# CanBus-UP-Schalter-Teil1.net
KiCad netlist of a schematic drawn in EAGLE
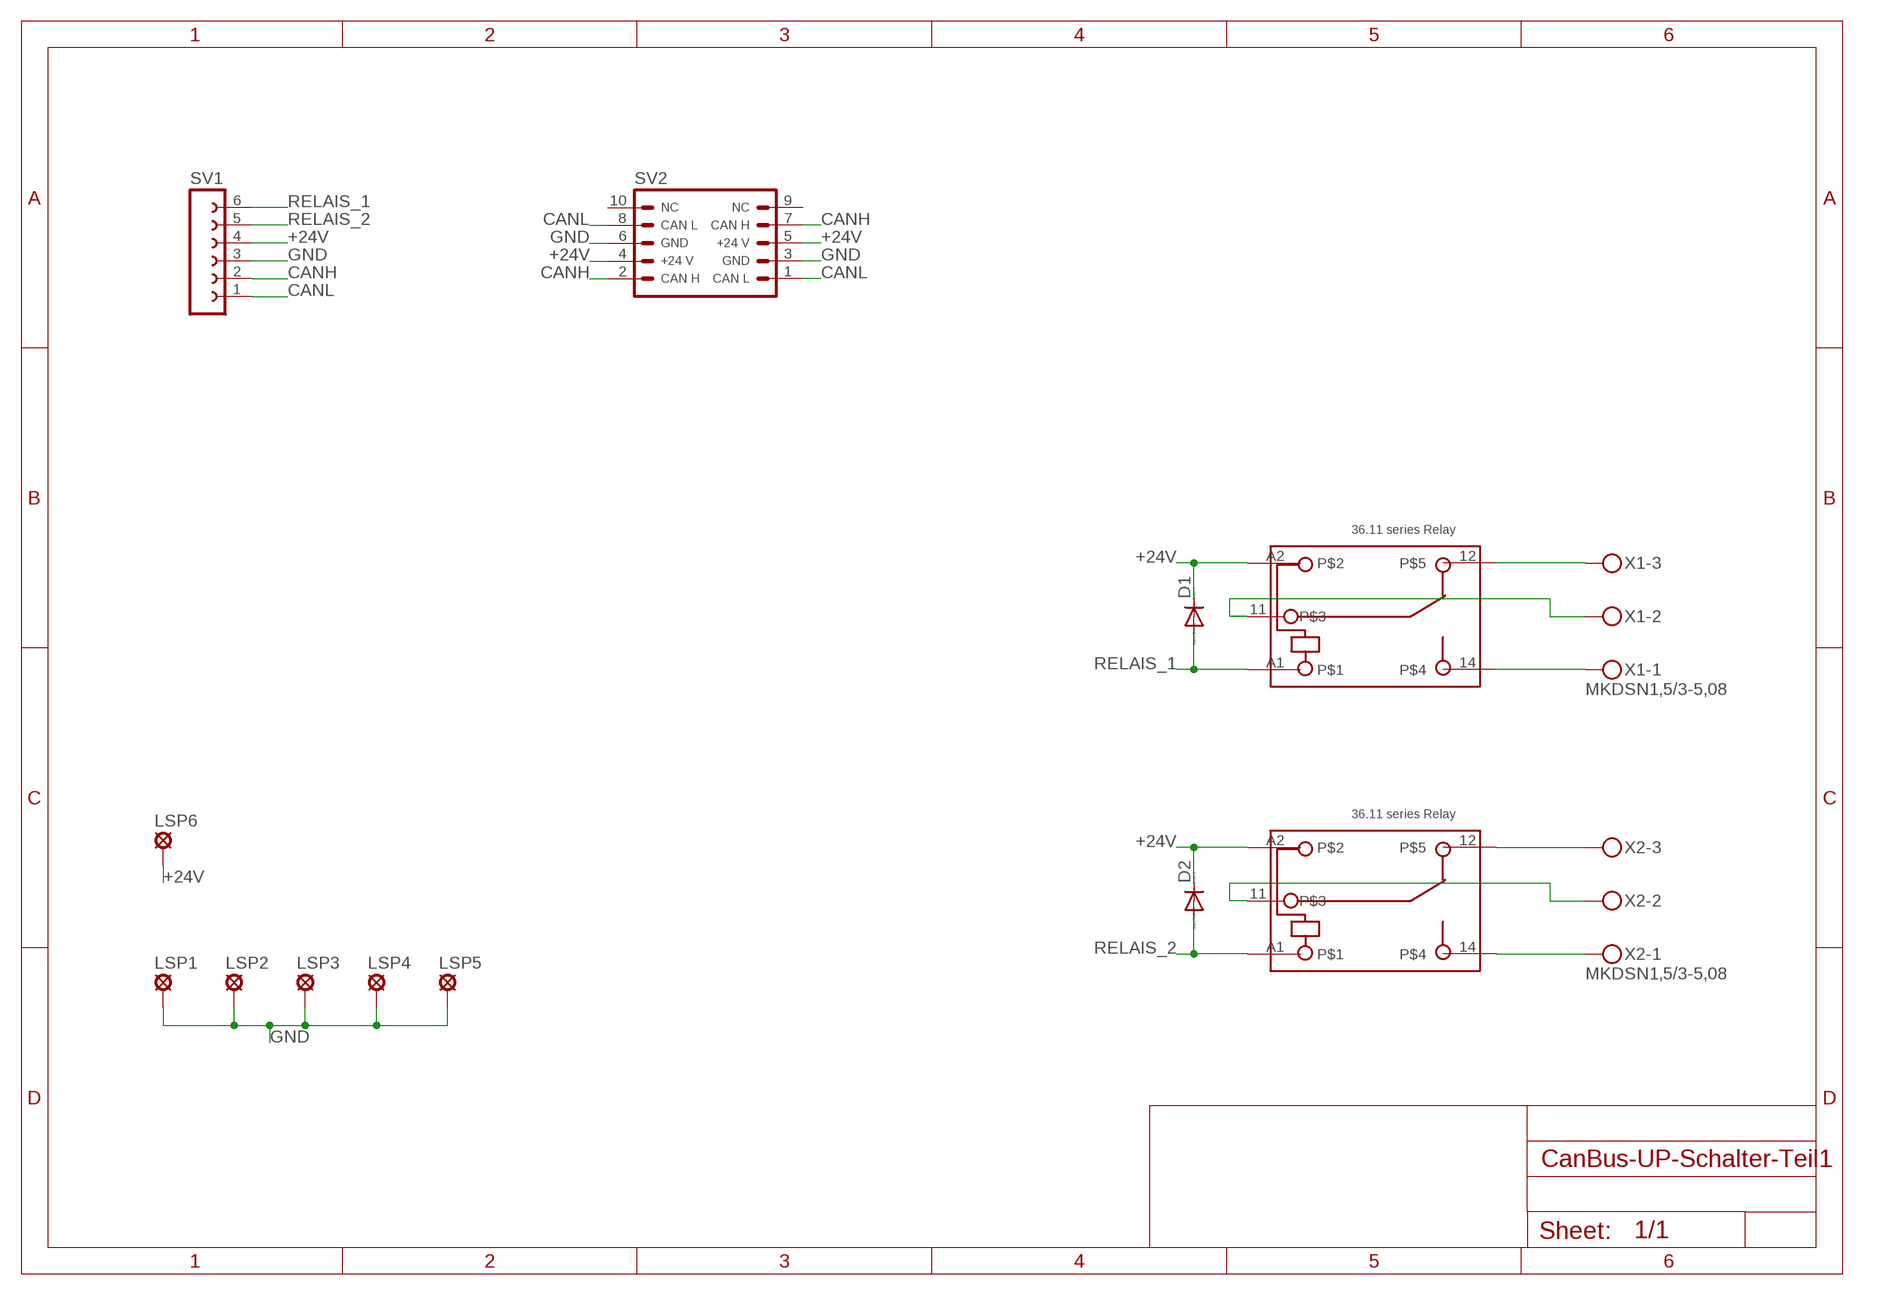
[diagram p0: schematic, sheet 1]

(export (version "E")
  (design (tool "Eeschema 10.0.6"))
  (components
    (comp (ref "D1")
      (value "DIODE-SOD323-R")
      (footprint "eagle-import:SOD323-R")
      (libsource (lib "eagle-import") (part "DIODE-SOD323-R"))
    )
    (comp (ref "D2")
      (value "DIODE-SOD323-R")
      (footprint "eagle-import:SOD323-R")
      (libsource (lib "eagle-import") (part "DIODE-SOD323-R"))
    )
    (comp (ref "K1")
      (value "36.11")
      (footprint "eagle-import:36.11")
      (libsource (lib "eagle-import") (part "36.11"))
    )
    (comp (ref "K2")
      (value "36.11")
      (footprint "eagle-import:36.11")
      (libsource (lib "eagle-import") (part "36.11"))
    )
    (comp (ref "LSP1")
      (value "LSP13")
      (footprint "eagle-import:LSP13")
      (libsource (lib "eagle-import") (part "LSP13"))
    )
    (comp (ref "LSP2")
      (value "LSP13")
      (footprint "eagle-import:LSP13")
      (libsource (lib "eagle-import") (part "LSP13"))
    )
    (comp (ref "LSP3")
      (value "LSP13")
      (footprint "eagle-import:LSP13")
      (libsource (lib "eagle-import") (part "LSP13"))
    )
    (comp (ref "LSP4")
      (value "LSP13")
      (footprint "eagle-import:LSP13")
      (libsource (lib "eagle-import") (part "LSP13"))
    )
    (comp (ref "LSP5")
      (value "LSP13")
      (footprint "eagle-import:LSP13")
      (libsource (lib "eagle-import") (part "LSP13"))
    )
    (comp (ref "LSP6")
      (value "LSP13")
      (footprint "eagle-import:LSP13")
      (libsource (lib "eagle-import") (part "LSP13"))
    )
    (comp (ref "SV1")
      (value "FE06-1")
      (footprint "eagle-import:FE06")
      (libsource (lib "eagle-import") (part "FE06-1"))
    )
    (comp (ref "SV2")
      (value "ML10L")
      (footprint "eagle-import:ML10L")
      (libsource (lib "eagle-import") (part "ML10L"))
    )
    (comp (ref "X1")
      (value "MKDSN1,5/3-5,08")
      (footprint "eagle-import:MKDSN1,5_3-5,08")
      (libsource (lib "eagle-import") (part "MKDSN1,5/3-5,08"))
    )
    (comp (ref "X2")
      (value "MKDSN1,5/3-5,08")
      (footprint "eagle-import:MKDSN1,5_3-5,08")
      (libsource (lib "eagle-import") (part "MKDSN1,5/3-5,08"))
    )
  )
  (nets
    (net (code "1") (name "/+24V") (class "Default")
      (node (ref "D1") (pin "C") (pinfunction "C_C") (pintype "passive"))
      (node (ref "D2") (pin "C") (pinfunction "C_C") (pintype "passive"))
      (node (ref "K1") (pin "A2") (pinfunction "P$2_A2") (pintype "passive"))
      (node (ref "K2") (pin "A2") (pinfunction "P$2_A2") (pintype "passive"))
      (node (ref "LSP6") (pin "MP") (pinfunction "MP_MP") (pintype "passive"))
      (node (ref "SV1") (pin "4") (pinfunction "4_4") (pintype "passive"))
      (node (ref "SV2") (pin "4") (pinfunction "4_4") (pintype "passive"))
      (node (ref "SV2") (pin "5") (pinfunction "5_5") (pintype "passive"))
    )
    (net (code "2") (name "/CANH") (class "Default")
      (node (ref "SV1") (pin "2") (pinfunction "2_2") (pintype "passive"))
      (node (ref "SV2") (pin "2") (pinfunction "2_2") (pintype "passive"))
      (node (ref "SV2") (pin "7") (pinfunction "7_7") (pintype "passive"))
    )
    (net (code "3") (name "/CANL") (class "Default")
      (node (ref "SV1") (pin "1") (pinfunction "1_1") (pintype "passive"))
      (node (ref "SV2") (pin "1") (pinfunction "1_1") (pintype "passive"))
      (node (ref "SV2") (pin "8") (pinfunction "8_8") (pintype "passive"))
    )
    (net (code "4") (name "/GND") (class "Default")
      (node (ref "LSP1") (pin "MP") (pinfunction "MP_MP") (pintype "passive"))
      (node (ref "LSP2") (pin "MP") (pinfunction "MP_MP") (pintype "passive"))
      (node (ref "LSP3") (pin "MP") (pinfunction "MP_MP") (pintype "passive"))
      (node (ref "LSP4") (pin "MP") (pinfunction "MP_MP") (pintype "passive"))
      (node (ref "LSP5") (pin "MP") (pinfunction "MP_MP") (pintype "passive"))
      (node (ref "SV1") (pin "3") (pinfunction "3_3") (pintype "passive"))
      (node (ref "SV2") (pin "3") (pinfunction "3_3") (pintype "passive"))
      (node (ref "SV2") (pin "6") (pinfunction "6_6") (pintype "passive"))
    )
    (net (code "5") (name "/RELAIS_1") (class "Default")
      (node (ref "D1") (pin "A") (pinfunction "A_A") (pintype "passive"))
      (node (ref "K1") (pin "A1") (pinfunction "P$1_A1") (pintype "passive"))
      (node (ref "SV1") (pin "6") (pinfunction "6_6") (pintype "passive"))
    )
    (net (code "6") (name "/RELAIS_2") (class "Default")
      (node (ref "D2") (pin "A") (pinfunction "A_A") (pintype "passive"))
      (node (ref "K2") (pin "A1") (pinfunction "P$1_A1") (pintype "passive"))
      (node (ref "SV1") (pin "5") (pinfunction "5_5") (pintype "passive"))
    )
    (net (code "7") (name "Net-(K1-P$3)") (class "Default")
      (node (ref "K1") (pin "11") (pinfunction "P$3_11") (pintype "passive"))
      (node (ref "X1") (pin "2") (pinfunction "KL_2") (pintype "passive"))
    )
    (net (code "8") (name "Net-(K1-P$4)") (class "Default")
      (node (ref "K1") (pin "14") (pinfunction "P$4_14") (pintype "passive"))
      (node (ref "X1") (pin "1") (pinfunction "KL_1") (pintype "passive"))
    )
    (net (code "9") (name "Net-(K1-P$5)") (class "Default")
      (node (ref "K1") (pin "12") (pinfunction "P$5_12") (pintype "passive"))
      (node (ref "X1") (pin "3") (pinfunction "KL_3") (pintype "passive"))
    )
    (net (code "10") (name "Net-(K2-P$3)") (class "Default")
      (node (ref "K2") (pin "11") (pinfunction "P$3_11") (pintype "passive"))
      (node (ref "X2") (pin "2") (pinfunction "KL_2") (pintype "passive"))
    )
    (net (code "11") (name "Net-(K2-P$4)") (class "Default")
      (node (ref "K2") (pin "14") (pinfunction "P$4_14") (pintype "passive"))
      (node (ref "X2") (pin "1") (pinfunction "KL_1") (pintype "passive"))
    )
    (net (code "12") (name "Net-(K2-P$5)") (class "Default")
      (node (ref "K2") (pin "12") (pinfunction "P$5_12") (pintype "passive"))
      (node (ref "X2") (pin "3") (pinfunction "KL_3") (pintype "passive"))
    )
    (net (code "13") (name "unconnected-(SV2-Pad9)") (class "Default")
      (node (ref "SV2") (pin "9") (pinfunction "9_9") (pintype "no_connect"))
    )
    (net (code "14") (name "unconnected-(SV2-Pad10)") (class "Default")
      (node (ref "SV2") (pin "10") (pinfunction "10_10") (pintype "no_connect"))
    )
  )
)
